# peripherals.net
KiCad netlist of a schematic drawn in Altium Designer
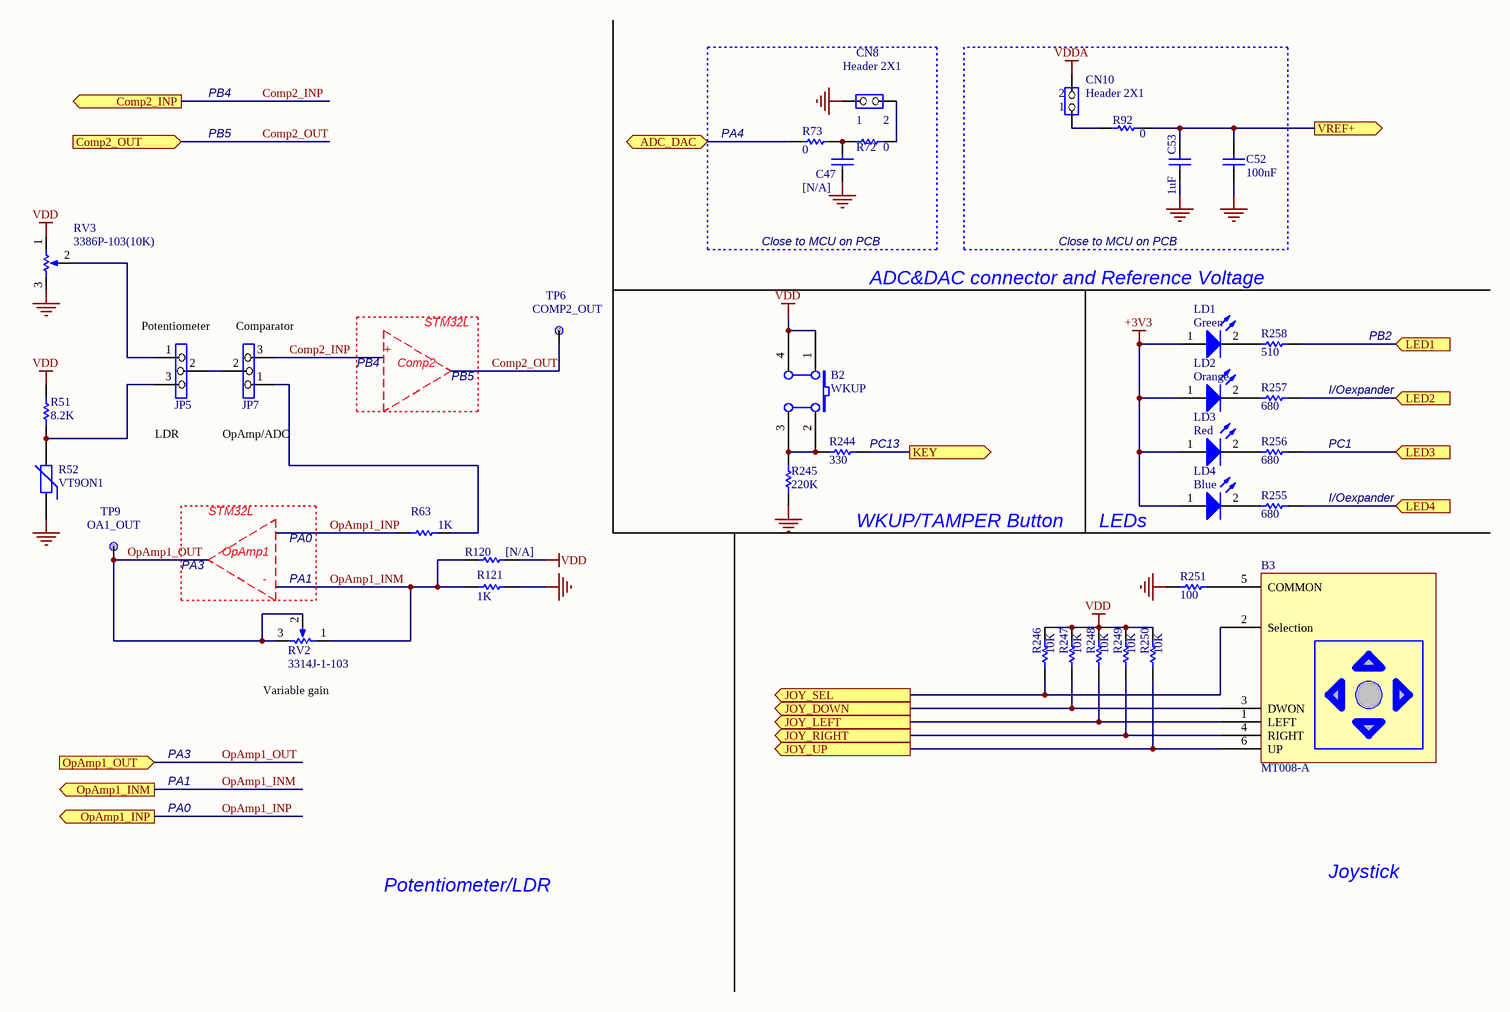
[diagram p0: peripherals.SchDoc]

(export (version "E")
  (design (tool "Eeschema 10.0.6"))
  (components
    (comp (ref "B2")
      (value "WKUP")
      (footprint "PB10")
      (description "SE PUSHBUTTON")
      (libsource (lib "Documents") (part "SW PUSHBUTTON"))
    )
    (comp (ref "B3") (value "MT008-A") (footprint "MT-008A") (libsource (lib "MB513") (part "MT-008A")))
    (comp (ref "C47")
      (value "[N/A]")
      (footprint "0603C")
      (description "Capacitor")
      (fields (field (name "PUBLISHER") "Altium Limited"))
      (libsource (lib "Miscellaneous Devices") (part "cap"))
    )
    (comp (ref "C52")
      (value "100nF")
      (footprint "0402C")
      (description "Capacitor")
      (fields (field (name "PUBLISHER") "Altium Limited"))
      (libsource (lib "Miscellaneous Devices") (part "Cap"))
    )
    (comp (ref "C53")
      (value "1uF")
      (footprint "0603C")
      (description "Capacitor")
      (fields (field (name "PUBLISHER") "Altium Limited"))
      (libsource (lib "Miscellaneous Devices") (part "CAP"))
    )
    (comp (ref "CN8") (value "Header 2X1") (footprint "SIP2") (libsource (lib "*") (part "JP2")))
    (comp (ref "CN10") (value "Header 2X1") (footprint "SIP2") (libsource (lib "*") (part "JP2")))
    (comp (ref "JP5")
      (value "Header 3X1")
      (footprint "SIP3")
      (libsource (lib "STR910_SCHLIB") (part "Jumper3"))
    )
    (comp (ref "JP7")
      (value "Header 3X1")
      (footprint "SIP3")
      (libsource (lib "STR910_SCHLIB") (part "Jumper3"))
    )
    (comp (ref "LD1")
      (value "Green")
      (footprint "0603D")
      (description "Typical RED, GREEN, YELLOW, AMBER GaAs LED")
      (fields (field (name "PUBLISHER") "Altium Limited"))
      (libsource (lib "Miscellaneous Devices") (part "LED2"))
    )
    (comp (ref "LD2")
      (value "Orange")
      (footprint "0603D")
      (description "Typical RED, GREEN, YELLOW, AMBER GaAs LED")
      (fields (field (name "PUBLISHER") "Altium Limited"))
      (libsource (lib "Miscellaneous Devices") (part "LED2"))
    )
    (comp (ref "LD3")
      (value "Red")
      (footprint "0603D")
      (description "Typical RED, GREEN, YELLOW, AMBER GaAs LED")
      (fields (field (name "PUBLISHER") "Altium Limited"))
      (libsource (lib "Miscellaneous Devices") (part "LED2"))
    )
    (comp (ref "LD4")
      (value "Blue")
      (footprint "0603D")
      (description "Typical RED, GREEN, YELLOW, AMBER GaAs LED")
      (fields (field (name "PUBLISHER") "Altium Limited"))
      (libsource (lib "Miscellaneous Devices") (part "LED2"))
    )
    (comp (ref "R51")
      (value "8.2K")
      (footprint "0402R")
      (description "Resistor")
      (fields (field (name "PUBLISHER") "Altium Limited"))
      (libsource (lib "Miscellaneous Devices") (part "Res1"))
    )
    (comp (ref "R52")
      (value "VT9ON1")
      (footprint "PVT901")
      (description "Varistor (Voltage-Sensitive Resistor)")
      (fields (field (name "PUBLISHER") "Altium Limited"))
      (libsource (lib "Miscellaneous Devices") (part "Res Varistor"))
    )
    (comp (ref "R63")
      (value "1K")
      (footprint "0402R")
      (description "Resistor")
      (fields (field (name "PUBLISHER") "Altium Limited"))
      (libsource (lib "Miscellaneous Devices") (part "Res1"))
    )
    (comp (ref "R72")
      (value "0")
      (footprint "0603R")
      (description "Resistor")
      (fields (field (name "PUBLISHER") "Altium Limited"))
      (libsource (lib "Miscellaneous Devices") (part "Res1"))
    )
    (comp (ref "R73")
      (value "0")
      (footprint "0603R")
      (description "Resistor")
      (fields (field (name "PUBLISHER") "Altium Limited"))
      (libsource (lib "Miscellaneous Devices") (part "Res1"))
    )
    (comp (ref "R92")
      (value "0")
      (footprint "0603R")
      (description "Resistor")
      (fields (field (name "PUBLISHER") "Altium Limited"))
      (libsource (lib "Miscellaneous Devices") (part "Res1"))
    )
    (comp (ref "R120")
      (value "[N/A]")
      (footprint "0603R")
      (description "Resistor")
      (fields (field (name "PUBLISHER") "Altium Limited"))
      (libsource (lib "Miscellaneous Devices") (part "Res1"))
    )
    (comp (ref "R121")
      (value "1K")
      (footprint "0402R")
      (description "Resistor")
      (fields (field (name "PUBLISHER") "Altium Limited"))
      (libsource (lib "Miscellaneous Devices") (part "Res1"))
    )
    (comp (ref "R244")
      (value "330")
      (footprint "0402R")
      (description "Resistor")
      (fields (field (name "PUBLISHER") "Altium Limited"))
      (libsource (lib "Miscellaneous Devices") (part "Res1"))
    )
    (comp (ref "R245")
      (value "220K")
      (footprint "0402R")
      (description "Resistor")
      (fields (field (name "PUBLISHER") "Altium Limited"))
      (libsource (lib "Miscellaneous Devices") (part "res1"))
    )
    (comp (ref "R246")
      (value "10K")
      (footprint "0402R")
      (description "Resistor")
      (fields (field (name "PUBLISHER") "Altium Limited"))
      (libsource (lib "Miscellaneous Devices") (part "Res1"))
    )
    (comp (ref "R247")
      (value "10K")
      (footprint "0402R")
      (description "Resistor")
      (fields (field (name "PUBLISHER") "Altium Limited"))
      (libsource (lib "Miscellaneous Devices") (part "Res1"))
    )
    (comp (ref "R248")
      (value "10K")
      (footprint "0402R")
      (description "Resistor")
      (fields (field (name "PUBLISHER") "Altium Limited"))
      (libsource (lib "Miscellaneous Devices") (part "Res1"))
    )
    (comp (ref "R249")
      (value "10K")
      (footprint "0402R")
      (description "Resistor")
      (fields (field (name "PUBLISHER") "Altium Limited"))
      (libsource (lib "Miscellaneous Devices") (part "Res1"))
    )
    (comp (ref "R250")
      (value "10K")
      (footprint "0402R")
      (description "Resistor")
      (fields (field (name "PUBLISHER") "Altium Limited"))
      (libsource (lib "Miscellaneous Devices") (part "Res1"))
    )
    (comp (ref "R251")
      (value "100")
      (footprint "0402R")
      (description "Resistor")
      (fields (field (name "PUBLISHER") "Altium Limited"))
      (libsource (lib "Miscellaneous Devices") (part "Res1"))
    )
    (comp (ref "R255")
      (value "680")
      (footprint "0402R")
      (description "Resistor")
      (fields (field (name "PUBLISHER") "Altium Limited"))
      (libsource (lib "Miscellaneous Devices") (part "Res1"))
    )
    (comp (ref "R256")
      (value "680")
      (footprint "0402R")
      (description "Resistor")
      (fields (field (name "PUBLISHER") "Altium Limited"))
      (libsource (lib "Miscellaneous Devices") (part "Res1"))
    )
    (comp (ref "R257")
      (value "680")
      (footprint "0402R")
      (description "Resistor")
      (fields (field (name "PUBLISHER") "Altium Limited"))
      (libsource (lib "Miscellaneous Devices") (part "Res1"))
    )
    (comp (ref "R258")
      (value "510")
      (footprint "0402R")
      (description "Resistor")
      (fields (field (name "PUBLISHER") "Altium Limited"))
      (libsource (lib "Miscellaneous Devices") (part "Res1"))
    )
    (comp (ref "RV2")
      (value "3314J-1-103")
      (footprint "PTF_3314J")
      (description "Potentiometer 10K")
      (libsource (lib "STR910_SCHLIB") (part "RV"))
    )
    (comp (ref "RV3")
      (value "3386P-103(10K)")
      (footprint "3386P")
      (description "Potentiometer 10K")
      (libsource (lib "STR910_SCHLIB") (part "RV"))
    )
    (comp (ref "TP6")
      (value "[N/A]")
      (footprint "TP")
      (fields (field (name "TP NAME") "COMP2_OUT"))
      (libsource (lib "*") (part "TP"))
    )
    (comp (ref "TP9")
      (value "[N/A]")
      (footprint "TP")
      (fields (field (name "TP NAME") "OA1_OUT"))
      (libsource (lib "*") (part "TP"))
    )
  )
  (nets
    (net (code "1") (name "+3V3") (class "Default")
      (node (ref "LD1") (pin "1") (pinfunction "A_1") (pintype "passive"))
      (node (ref "LD2") (pin "1") (pinfunction "A_1") (pintype "passive"))
      (node (ref "LD3") (pin "1") (pinfunction "A_1") (pintype "passive"))
      (node (ref "LD4") (pin "1") (pinfunction "A_1") (pintype "passive"))
    )
    (net (code "2") (name "/ADC_DAC") (class "Default")
      (node (ref "R73") (pin "1") (pinfunction "1_1") (pintype "passive"))
    )
    (net (code "3") (name "/Comp2_INP") (class "Default") (node (ref "JP7") (pin "3") (pintype "passive")))
    (net (code "4") (name "/Comp2_OUT") (class "Default")
      (node (ref "TP6") (pin "1") (pinfunction "1_1") (pintype "passive"))
    )
    (net (code "5") (name "/JOY_DOWN") (class "Default")
      (node (ref "B3") (pin "3") (pinfunction "DWON_3") (pintype "passive"))
      (node (ref "R247") (pin "1") (pinfunction "1_1") (pintype "passive"))
    )
    (net (code "6") (name "/JOY_LEFT") (class "Default")
      (node (ref "B3") (pin "1") (pinfunction "LEFT_1") (pintype "passive"))
      (node (ref "R248") (pin "1") (pinfunction "1_1") (pintype "passive"))
    )
    (net (code "7") (name "/JOY_RIGHT") (class "Default")
      (node (ref "B3") (pin "4") (pinfunction "RIGHT_4") (pintype "passive"))
      (node (ref "R249") (pin "1") (pinfunction "1_1") (pintype "passive"))
    )
    (net (code "8") (name "/JOY_SEL") (class "Default")
      (node (ref "B3") (pin "2") (pinfunction "Selection_2") (pintype "passive"))
      (node (ref "R246") (pin "2") (pinfunction "2_2") (pintype "passive"))
    )
    (net (code "9") (name "/JOY_UP") (class "Default")
      (node (ref "B3") (pin "6") (pinfunction "UP_6") (pintype "passive"))
      (node (ref "R250") (pin "1") (pinfunction "1_1") (pintype "passive"))
    )
    (net (code "10") (name "/KEY") (class "Default")
      (node (ref "R244") (pin "2") (pinfunction "2_2") (pintype "passive"))
    )
    (net (code "11") (name "/LED1") (class "Default")
      (node (ref "R258") (pin "1") (pinfunction "1_1") (pintype "passive"))
    )
    (net (code "12") (name "/LED2") (class "Default")
      (node (ref "R257") (pin "1") (pinfunction "1_1") (pintype "passive"))
    )
    (net (code "13") (name "/LED3") (class "Default")
      (node (ref "R256") (pin "1") (pinfunction "1_1") (pintype "passive"))
    )
    (net (code "14") (name "/LED4") (class "Default")
      (node (ref "R255") (pin "1") (pinfunction "1_1") (pintype "passive"))
    )
    (net (code "15") (name "/OpAmp1_INM") (class "Default")
      (node (ref "R120") (pin "1") (pinfunction "1_1") (pintype "passive"))
      (node (ref "R121") (pin "2") (pinfunction "2_2") (pintype "passive"))
      (node (ref "RV2") (pin "1") (pinfunction "BOT_1") (pintype "passive"))
    )
    (net (code "16") (name "/OpAmp1_INP") (class "Default")
      (node (ref "R63") (pin "2") (pinfunction "2_2") (pintype "passive"))
    )
    (net (code "17") (name "/OpAmp1_OUT") (class "Default")
      (node (ref "RV2") (pin "2") (pinfunction "TAP_2") (pintype "passive"))
      (node (ref "RV2") (pin "3") (pinfunction "TOP_3") (pintype "passive"))
      (node (ref "TP9") (pin "1") (pinfunction "1_1") (pintype "passive"))
    )
    (net (code "18") (name "/VREF+") (class "Default")
      (node (ref "C52") (pin "2") (pinfunction "2_2") (pintype "passive"))
      (node (ref "C53") (pin "1") (pinfunction "1_1") (pintype "passive"))
      (node (ref "R92") (pin "2") (pinfunction "2_2") (pintype "passive"))
    )
    (net (code "19") (name "GND") (class "Default")
      (node (ref "C47") (pin "1") (pinfunction "1_1") (pintype "passive"))
      (node (ref "C52") (pin "1") (pinfunction "1_1") (pintype "passive"))
      (node (ref "C53") (pin "2") (pinfunction "2_2") (pintype "passive"))
      (node (ref "CN8") (pin "1") (pinfunction "COMMON_1") (pintype "passive"))
      (node (ref "R121") (pin "1") (pinfunction "1_1") (pintype "passive"))
      (node (ref "R245") (pin "2") (pinfunction "2_2") (pintype "passive"))
      (node (ref "R251") (pin "1") (pinfunction "1_1") (pintype "passive"))
      (node (ref "R52") (pin "1") (pinfunction "1_1") (pintype "passive"))
      (node (ref "RV3") (pin "3") (pinfunction "TOP_3") (pintype "passive"))
    )
    (net (code "20") (name "Net-(B2-B0)") (class "Default")
      (node (ref "B2") (pin "2") (pinfunction "B0_2") (pintype "passive"))
      (node (ref "B2") (pin "3") (pinfunction "B1_3") (pintype "passive"))
      (node (ref "R244") (pin "1") (pinfunction "1_1") (pintype "passive"))
      (node (ref "R245") (pin "1") (pinfunction "1_1") (pintype "passive"))
    )
    (net (code "21") (name "Net-(B3-COMMON)") (class "Default")
      (node (ref "B3") (pin "5") (pinfunction "COMMON_5") (pintype "passive"))
      (node (ref "R251") (pin "2") (pinfunction "2_2") (pintype "passive"))
    )
    (net (code "22") (name "Net-(C47-Pad2)") (class "Default")
      (node (ref "C47") (pin "2") (pinfunction "2_2") (pintype "passive"))
      (node (ref "R72") (pin "1") (pinfunction "1_1") (pintype "passive"))
      (node (ref "R73") (pin "2") (pinfunction "2_2") (pintype "passive"))
    )
    (net (code "23") (name "Net-(CN8-NO)") (class "Default")
      (node (ref "CN8") (pin "2") (pinfunction "NO_2") (pintype "passive"))
      (node (ref "R72") (pin "2") (pinfunction "2_2") (pintype "passive"))
    )
    (net (code "24") (name "Net-(CN10-COMMON)") (class "Default")
      (node (ref "CN10") (pin "1") (pinfunction "COMMON_1") (pintype "passive"))
      (node (ref "R92") (pin "1") (pinfunction "1_1") (pintype "passive"))
    )
    (net (code "25") (name "Net-(JP5-Pad2)") (class "Default")
      (node (ref "JP5") (pin "2") (pintype "passive"))
      (node (ref "JP7") (pin "2") (pintype "passive"))
    )
    (net (code "26") (name "Net-(JP5-Pad3)") (class "Default")
      (node (ref "JP5") (pin "3") (pintype "passive"))
      (node (ref "R51") (pin "1") (pinfunction "1_1") (pintype "passive"))
      (node (ref "R52") (pin "2") (pinfunction "2_2") (pintype "passive"))
    )
    (net (code "27") (name "Net-(JP7-Pad1)") (class "Default")
      (node (ref "JP7") (pin "1") (pintype "passive"))
      (node (ref "R63") (pin "1") (pinfunction "1_1") (pintype "passive"))
    )
    (net (code "28") (name "Net-(LD1-K)") (class "Default")
      (node (ref "LD1") (pin "2") (pinfunction "K_2") (pintype "passive"))
      (node (ref "R258") (pin "2") (pinfunction "2_2") (pintype "passive"))
    )
    (net (code "29") (name "Net-(LD2-K)") (class "Default")
      (node (ref "LD2") (pin "2") (pinfunction "K_2") (pintype "passive"))
      (node (ref "R257") (pin "2") (pinfunction "2_2") (pintype "passive"))
    )
    (net (code "30") (name "Net-(LD3-K)") (class "Default")
      (node (ref "LD3") (pin "2") (pinfunction "K_2") (pintype "passive"))
      (node (ref "R256") (pin "2") (pinfunction "2_2") (pintype "passive"))
    )
    (net (code "31") (name "Net-(LD4-K)") (class "Default")
      (node (ref "LD4") (pin "2") (pinfunction "K_2") (pintype "passive"))
      (node (ref "R255") (pin "2") (pinfunction "2_2") (pintype "passive"))
    )
    (net (code "32") (name "Net-(RV3-TAP)") (class "Default")
      (node (ref "JP5") (pin "1") (pintype "passive"))
      (node (ref "RV3") (pin "2") (pinfunction "TAP_2") (pintype "passive"))
    )
    (net (code "33") (name "VDD") (class "Default")
      (node (ref "B2") (pin "1") (pinfunction "A0_1") (pintype "passive"))
      (node (ref "B2") (pin "4") (pinfunction "A1_4") (pintype "passive"))
      (node (ref "R120") (pin "2") (pinfunction "2_2") (pintype "passive"))
      (node (ref "R246") (pin "1") (pinfunction "1_1") (pintype "passive"))
      (node (ref "R247") (pin "2") (pinfunction "2_2") (pintype "passive"))
      (node (ref "R248") (pin "2") (pinfunction "2_2") (pintype "passive"))
      (node (ref "R249") (pin "2") (pinfunction "2_2") (pintype "passive"))
      (node (ref "R250") (pin "2") (pinfunction "2_2") (pintype "passive"))
      (node (ref "R51") (pin "2") (pinfunction "2_2") (pintype "passive"))
      (node (ref "RV3") (pin "1") (pinfunction "BOT_1") (pintype "passive"))
    )
    (net (code "34") (name "VDDA") (class "Default")
      (node (ref "CN10") (pin "2") (pinfunction "NO_2") (pintype "passive"))
    )
  )
)
